# DCDC_12V_Servo.net
KiCad netlist of a schematic drawn in Altium Designer
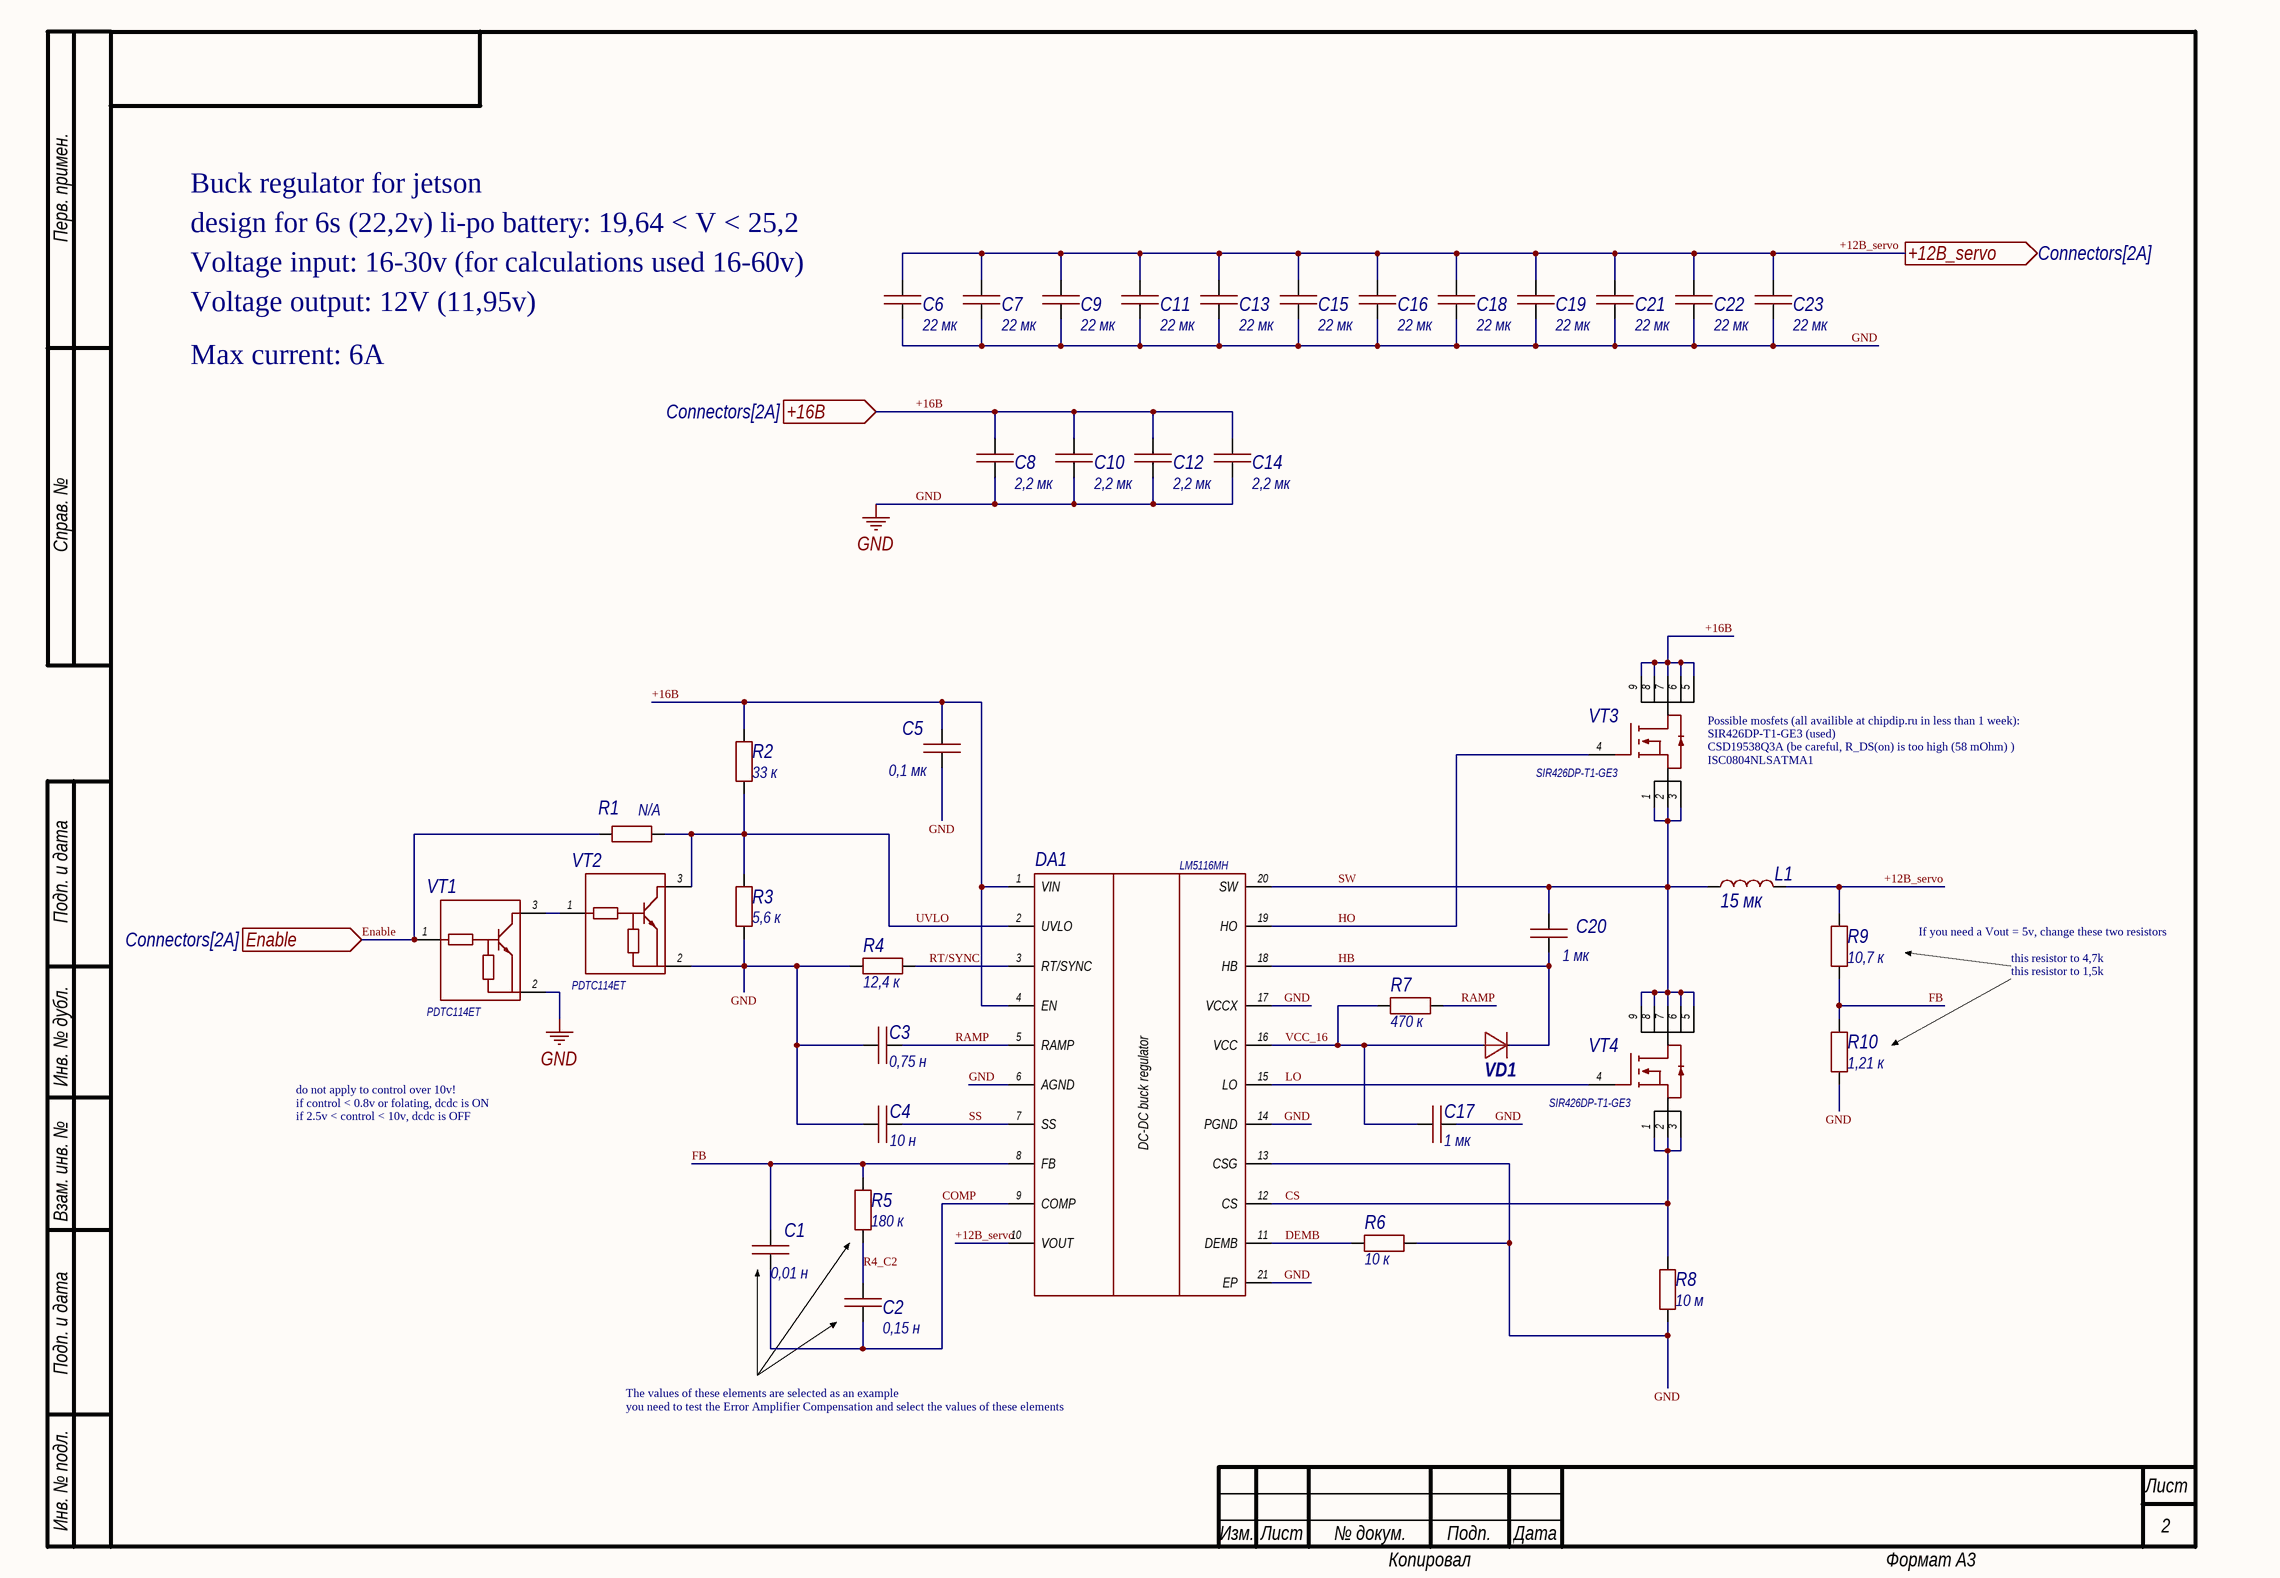
[diagram p0: DCDC_12V_Servo.SchDoc]

(export (version "E")
  (design (tool "Eeschema 10.0.6"))
  (components
    (comp (ref "C1")
      (value "0,01 н")
      (footprint "0603C")
      (description "Конденсатор")
      (fields
        (field (name "PART NUMBER") "Capacitor_0,01n_10_50V_X7R_0603C")
        (field (name "TOLERANCE") "0,1")
      )
      (libsource (lib "Hydrolib") (part "Capacitor"))
    )
    (comp (ref "C2")
      (value "0,15 н")
      (footprint "0603C")
      (description "Конденсатор")
      (fields
        (field (name "PART NUMBER") "Capacitor_0,15n_10_50V_X7R_0603C")
        (field (name "TOLERANCE") "0,1")
      )
      (libsource (lib "Hydrolib") (part "Capacitor"))
    )
    (comp (ref "C3")
      (value "0,75 н")
      (footprint "0603C")
      (description "Конденсатор")
      (fields
        (field (name "PART NUMBER") "Capacitor_0,75n_10_50V_X7R_0603C")
        (field (name "TOLERANCE") "0,1")
      )
      (libsource (lib "Hydrolib") (part "Capacitor"))
    )
    (comp (ref "C4")
      (value "10 н")
      (footprint "0603C")
      (description "Конденсатор")
      (fields (field (name "PART NUMBER") "Capacitor_10n_10_50V_X7R_0603C") (field (name "TOLERANCE") "0,1"))
      (libsource (lib "Hydrolib") (part "Capacitor"))
    )
    (comp (ref "C5")
      (value "0,1 мк")
      (footprint "0603C")
      (description "Конденсатор")
      (fields (field (name "PART NUMBER") "Capacitor_0,1u_10_50V_X7R_0603C") (field (name "TOLERANCE") "0,1"))
      (libsource (lib "Hydrolib") (part "Capacitor"))
    )
    (comp (ref "C6")
      (value "22 мк")
      (footprint "1210C")
      (description "Конденсатор")
      (fields (field (name "PART NUMBER") "Capacitor_22u_10_25V_X7R_1210C") (field (name "TOLERANCE") "0,1"))
      (libsource (lib "Hydrolib") (part "Capacitor"))
    )
    (comp (ref "C7")
      (value "22 мк")
      (footprint "1210C")
      (description "Конденсатор")
      (fields (field (name "PART NUMBER") "Capacitor_22u_10_25V_X7R_1210C") (field (name "TOLERANCE") "0,1"))
      (libsource (lib "Hydrolib") (part "Capacitor"))
    )
    (comp (ref "C8")
      (value "2,2 мк")
      (footprint "1206C")
      (description "Конденсатор")
      (fields (field (name "PART NUMBER") "Capacitor_2,2u_10_50V_X7R_1206C") (field (name "TOLERANCE") "0,1"))
      (libsource (lib "Hydrolib") (part "Capacitor"))
    )
    (comp (ref "C9")
      (value "22 мк")
      (footprint "1210C")
      (description "Конденсатор")
      (fields (field (name "PART NUMBER") "Capacitor_22u_10_25V_X7R_1210C") (field (name "TOLERANCE") "0,1"))
      (libsource (lib "Hydrolib") (part "Capacitor"))
    )
    (comp (ref "C10")
      (value "2,2 мк")
      (footprint "1206C")
      (description "Конденсатор")
      (fields (field (name "PART NUMBER") "Capacitor_2,2u_10_50V_X7R_1206C") (field (name "TOLERANCE") "0,1"))
      (libsource (lib "Hydrolib") (part "Capacitor"))
    )
    (comp (ref "C11")
      (value "22 мк")
      (footprint "1210C")
      (description "Конденсатор")
      (fields (field (name "PART NUMBER") "Capacitor_22u_10_25V_X7R_1210C") (field (name "TOLERANCE") "0,1"))
      (libsource (lib "Hydrolib") (part "Capacitor"))
    )
    (comp (ref "C12")
      (value "2,2 мк")
      (footprint "1206C")
      (description "Конденсатор")
      (fields (field (name "PART NUMBER") "Capacitor_2,2u_10_50V_X7R_1206C") (field (name "TOLERANCE") "0,1"))
      (libsource (lib "Hydrolib") (part "Capacitor"))
    )
    (comp (ref "C13")
      (value "22 мк")
      (footprint "1210C")
      (description "Конденсатор")
      (fields (field (name "PART NUMBER") "Capacitor_22u_10_25V_X7R_1210C") (field (name "TOLERANCE") "0,1"))
      (libsource (lib "Hydrolib") (part "Capacitor"))
    )
    (comp (ref "C14")
      (value "2,2 мк")
      (footprint "1206C")
      (description "Конденсатор")
      (fields (field (name "PART NUMBER") "Capacitor_2,2u_10_50V_X7R_1206C") (field (name "TOLERANCE") "0,1"))
      (libsource (lib "Hydrolib") (part "Capacitor"))
    )
    (comp (ref "C15")
      (value "22 мк")
      (footprint "1210C")
      (description "Конденсатор")
      (fields (field (name "PART NUMBER") "Capacitor_22u_10_25V_X7R_1210C") (field (name "TOLERANCE") "0,1"))
      (libsource (lib "Hydrolib") (part "Capacitor"))
    )
    (comp (ref "C16")
      (value "22 мк")
      (footprint "1210C")
      (description "Конденсатор")
      (fields (field (name "PART NUMBER") "Capacitor_22u_10_25V_X7R_1210C") (field (name "TOLERANCE") "0,1"))
      (libsource (lib "Hydrolib") (part "Capacitor"))
    )
    (comp (ref "C17")
      (value "1 мк")
      (footprint "0603C")
      (description "Конденсатор")
      (fields (field (name "PART NUMBER") "Capacitor_1u_10_50V_X7R_0603C") (field (name "TOLERANCE") "0,1"))
      (libsource (lib "Hydrolib") (part "Capacitor"))
    )
    (comp (ref "C18")
      (value "22 мк")
      (footprint "1210C")
      (description "Конденсатор")
      (fields (field (name "PART NUMBER") "Capacitor_22u_10_25V_X7R_1210C") (field (name "TOLERANCE") "0,1"))
      (libsource (lib "Hydrolib") (part "Capacitor"))
    )
    (comp (ref "C19")
      (value "22 мк")
      (footprint "1210C")
      (description "Конденсатор")
      (fields (field (name "PART NUMBER") "Capacitor_22u_10_25V_X7R_1210C") (field (name "TOLERANCE") "0,1"))
      (libsource (lib "Hydrolib") (part "Capacitor"))
    )
    (comp (ref "C20")
      (value "1 мк")
      (footprint "0603C")
      (description "Конденсатор")
      (fields (field (name "PART NUMBER") "Capacitor_1u_10_50V_X7R_0603C") (field (name "TOLERANCE") "0,1"))
      (libsource (lib "Hydrolib") (part "Capacitor"))
    )
    (comp (ref "C21")
      (value "22 мк")
      (footprint "1210C")
      (description "Конденсатор")
      (fields (field (name "PART NUMBER") "Capacitor_22u_10_25V_X7R_1210C") (field (name "TOLERANCE") "0,1"))
      (libsource (lib "Hydrolib") (part "Capacitor"))
    )
    (comp (ref "C22")
      (value "22 мк")
      (footprint "1210C")
      (description "Конденсатор")
      (fields (field (name "PART NUMBER") "Capacitor_22u_10_25V_X7R_1210C") (field (name "TOLERANCE") "0,1"))
      (libsource (lib "Hydrolib") (part "Capacitor"))
    )
    (comp (ref "C23")
      (value "22 мк")
      (footprint "1210C")
      (description "Конденсатор")
      (fields (field (name "PART NUMBER") "Capacitor_22u_10_25V_X7R_1210C") (field (name "TOLERANCE") "0,1"))
      (libsource (lib "Hydrolib") (part "Capacitor"))
    )
    (comp (ref "DA1")
      (value "LM5116MH")
      (footprint "HTSSOP-20")
      (description "dc-dc понижающий adj 6-100v")
      (fields (field (name "MANUFACTURER_PART_NUMBER") "LM5116MH/NOPB"))
      (libsource (lib "Hydrolib") (part "LM5116MH"))
    )
    (comp (ref "L1")
      (value "15 мк")
      (footprint "SPRH127")
      (description "Индуктивность на 15 мкГн, номинальный ток 8,4 А")
      (fields (field (name "PART NUMBER") "CDSPRH127-150M"))
      (libsource (lib "Hydrolib") (part "Inductance"))
    )
    (comp (ref "R1")
      (value "N/A")
      (footprint "0603R")
      (description "посадочное место 0603 под перемычку")
      (fields (field (name "PART NUMBER") "res_0603_N/A") (field (name "TOLERANCE") "1%"))
      (libsource (lib "Hydrolib") (part "Resistor"))
    )
    (comp (ref "R2")
      (value "33 к")
      (footprint "0603R")
      (description "Резистор номиналом 33 кОм и точностью 1%")
      (fields (field (name "PART NUMBER") "Resistor_33k_1_0603") (field (name "TOLERANCE") "1%"))
      (libsource (lib "") (part "Resistor_1"))
    )
    (comp (ref "R3")
      (value "5,6 к")
      (footprint "0603R")
      (description "Резистор номиналом 5,6 кОм 1%")
      (fields (field (name "PART NUMBER") "Resistor_5.6k_1_0603") (field (name "TOLERANCE") "1%"))
      (libsource (lib "") (part "Resistor_1"))
    )
    (comp (ref "R4")
      (value "12,4 к")
      (footprint "0603R")
      (description "Резистор номиналом 12,4 кОм и точностью 1%")
      (fields (field (name "PART NUMBER") "Resistor_12.4k_1_0603") (field (name "TOLERANCE") "1%"))
      (libsource (lib "Hydrolib") (part "Resistor"))
    )
    (comp (ref "R5")
      (value "180 к")
      (footprint "0603R")
      (description "Резистор номиналом 180 кОм и точностью 1%")
      (fields (field (name "PART NUMBER") "Resistor_180k_1_0603") (field (name "TOLERANCE") "1%"))
      (libsource (lib "") (part "Resistor_1"))
    )
    (comp (ref "R6")
      (value "10 к")
      (footprint "0603R")
      (description "Резистор номиналом 10 кОм и точностью 1%")
      (fields (field (name "PART NUMBER") "Resistor_10k_1_0603") (field (name "TOLERANCE") "1%"))
      (libsource (lib "Hydrolib") (part "Resistor"))
    )
    (comp (ref "R7")
      (value "470 к")
      (footprint "0603R")
      (description "Резистор номиналом 470 кОм и точностью 1%")
      (fields (field (name "PART NUMBER") "Resistor_470k_1_0603") (field (name "TOLERANCE") "1%"))
      (libsource (lib "Hydrolib") (part "Resistor"))
    )
    (comp (ref "R8")
      (value "10 м")
      (footprint "1210R")
      (description "Резистор номиналом 10 мОм, точностью 1%, 0.5Вт")
      (fields (field (name "PART NUMBER") "RL1210FR-070R01L") (field (name "TOLERANCE") "1%"))
      (libsource (lib "") (part "Resistor_1"))
    )
    (comp (ref "R9")
      (value "10,7 к")
      (footprint "0603R")
      (description "Резистор номиналом 10,7 кОм и точностью 1%")
      (fields (field (name "PART NUMBER") "Resistor_10.7k_1_0603") (field (name "TOLERANCE") "1%"))
      (libsource (lib "") (part "Resistor_1"))
    )
    (comp (ref "R10")
      (value "1,21 к")
      (footprint "0603R")
      (description "Резистор номиналом 1,21 кОм и точностью 1%")
      (fields (field (name "PART NUMBER") "Resistor_1.21k_1_0603") (field (name "TOLERANCE") "1%"))
      (libsource (lib "") (part "Resistor_1"))
    )
    (comp (ref "VD1")
      (value "ES1D-E3/61T")
      (footprint "SMA")
      (description "Диод 1A 200V")
      (libsource (lib "Hydrolib") (part "Rectifier_diode"))
    )
    (comp (ref "VT1")
      (value "PDTC114ET")
      (footprint "SOT23-3")
      (description "цифровой npn 50в 100мА")
      (libsource (lib "Hydrolib") (part "PDTC114ET"))
    )
    (comp (ref "VT2")
      (value "PDTC114ET")
      (footprint "SOT23-3")
      (description "цифровой npn 50в 100мА")
      (libsource (lib "Hydrolib") (part "PDTC114ET"))
    )
    (comp (ref "VT3")
      (value "SIR426DP-T1-GE3")
      (footprint "PowerPAK_SO-8")
      (description "Транзистор полевой MOSFET N-канальный 40В 41.7Вт")
      (libsource (lib "Hydrolib") (part "SIR426DP-T1-GE3"))
    )
    (comp (ref "VT4")
      (value "SIR426DP-T1-GE3")
      (footprint "PowerPAK_SO-8")
      (description "Транзистор полевой MOSFET N-канальный 40В 41.7Вт")
      (libsource (lib "Hydrolib") (part "SIR426DP-T1-GE3"))
    )
  )
  (nets
    (net (code "1") (name "/+12В_servo") (class "Default")
      (node (ref "C11") (pin "2") (pinfunction "2_2") (pintype "passive"))
      (node (ref "C13") (pin "2") (pinfunction "2_2") (pintype "passive"))
      (node (ref "C15") (pin "2") (pinfunction "2_2") (pintype "passive"))
      (node (ref "C16") (pin "2") (pinfunction "2_2") (pintype "passive"))
      (node (ref "C18") (pin "2") (pinfunction "2_2") (pintype "passive"))
      (node (ref "C19") (pin "2") (pinfunction "2_2") (pintype "passive"))
      (node (ref "C21") (pin "2") (pinfunction "2_2") (pintype "passive"))
      (node (ref "C22") (pin "2") (pinfunction "2_2") (pintype "passive"))
      (node (ref "C23") (pin "2") (pinfunction "2_2") (pintype "passive"))
      (node (ref "C6") (pin "2") (pinfunction "2_2") (pintype "passive"))
      (node (ref "C7") (pin "2") (pinfunction "2_2") (pintype "passive"))
      (node (ref "C9") (pin "2") (pinfunction "2_2") (pintype "passive"))
      (node (ref "DA1") (pin "10") (pinfunction "VOUT_10") (pintype "passive"))
      (node (ref "L1") (pin "2") (pinfunction "2_2") (pintype "passive"))
      (node (ref "R9") (pin "2") (pinfunction "2_2") (pintype "passive"))
    )
    (net (code "2") (name "/+16В") (class "Default")
      (node (ref "C10") (pin "2") (pinfunction "2_2") (pintype "passive"))
      (node (ref "C12") (pin "2") (pinfunction "2_2") (pintype "passive"))
      (node (ref "C14") (pin "2") (pinfunction "2_2") (pintype "passive"))
      (node (ref "C5") (pin "2") (pinfunction "2_2") (pintype "passive"))
      (node (ref "C8") (pin "2") (pinfunction "2_2") (pintype "passive"))
      (node (ref "DA1") (pin "1") (pinfunction "VIN_1") (pintype "passive"))
      (node (ref "DA1") (pin "4") (pinfunction "EN_4") (pintype "passive"))
      (node (ref "R2") (pin "2") (pinfunction "2_2") (pintype "passive"))
      (node (ref "VT3") (pin "5") (pinfunction "5_5") (pintype "passive"))
      (node (ref "VT3") (pin "6") (pinfunction "6_6") (pintype "passive"))
      (node (ref "VT3") (pin "7") (pinfunction "7_7") (pintype "passive"))
      (node (ref "VT3") (pin "8") (pinfunction "8_8") (pintype "passive"))
      (node (ref "VT3") (pin "9") (pinfunction "9_9") (pintype "passive"))
    )
    (net (code "3") (name "/COMP") (class "Default")
      (node (ref "C1") (pin "1") (pinfunction "1_1") (pintype "passive"))
      (node (ref "C2") (pin "1") (pinfunction "1_1") (pintype "passive"))
      (node (ref "DA1") (pin "9") (pinfunction "COMP_9") (pintype "passive"))
    )
    (net (code "4") (name "/CS") (class "Default")
      (node (ref "DA1") (pin "12") (pinfunction "CS_12") (pintype "passive"))
      (node (ref "R8") (pin "2") (pinfunction "2_2") (pintype "passive"))
      (node (ref "VT4") (pin "1") (pinfunction "1_1") (pintype "passive"))
      (node (ref "VT4") (pin "2") (pinfunction "2_2") (pintype "passive"))
      (node (ref "VT4") (pin "3") (pinfunction "3_3") (pintype "passive"))
    )
    (net (code "5") (name "/DEMB") (class "Default")
      (node (ref "DA1") (pin "11") (pinfunction "DEMB_11") (pintype "passive"))
      (node (ref "R6") (pin "1") (pinfunction "1_1") (pintype "passive"))
    )
    (net (code "6") (name "/Enable") (class "Default")
      (node (ref "R1") (pin "1") (pinfunction "1_1") (pintype "passive"))
      (node (ref "VT1") (pin "1") (pinfunction "B_1") (pintype "passive"))
    )
    (net (code "7") (name "/FB") (class "Default")
      (node (ref "C1") (pin "2") (pinfunction "2_2") (pintype "passive"))
      (node (ref "DA1") (pin "8") (pinfunction "FB_8") (pintype "passive"))
      (node (ref "R10") (pin "2") (pinfunction "2_2") (pintype "passive"))
      (node (ref "R5") (pin "2") (pinfunction "2_2") (pintype "passive"))
      (node (ref "R9") (pin "1") (pinfunction "1_1") (pintype "passive"))
    )
    (net (code "8") (name "/HB") (class "Default")
      (node (ref "C20") (pin "1") (pinfunction "1_1") (pintype "passive"))
      (node (ref "DA1") (pin "18") (pinfunction "HB_18") (pintype "passive"))
      (node (ref "VD1") (pin "2") (pinfunction "2_2") (pintype "passive"))
    )
    (net (code "9") (name "/HO") (class "Default")
      (node (ref "DA1") (pin "19") (pinfunction "HO_19") (pintype "passive"))
      (node (ref "VT3") (pin "4") (pinfunction "4_4") (pintype "passive"))
    )
    (net (code "10") (name "/LO") (class "Default")
      (node (ref "DA1") (pin "15") (pinfunction "LO_15") (pintype "passive"))
      (node (ref "VT4") (pin "4") (pinfunction "4_4") (pintype "passive"))
    )
    (net (code "11") (name "/R4_C2") (class "Default")
      (node (ref "C2") (pin "2") (pinfunction "2_2") (pintype "passive"))
      (node (ref "R5") (pin "1") (pinfunction "1_1") (pintype "passive"))
    )
    (net (code "12") (name "/RAMP") (class "Default")
      (node (ref "C3") (pin "2") (pinfunction "2_2") (pintype "passive"))
      (node (ref "DA1") (pin "5") (pinfunction "RAMP_5") (pintype "passive"))
      (node (ref "R7") (pin "2") (pinfunction "2_2") (pintype "passive"))
    )
    (net (code "13") (name "/RT{slash}SYNC") (class "Default")
      (node (ref "DA1") (pin "3") (pinfunction "RT/SYNC_3") (pintype "passive"))
      (node (ref "R4") (pin "2") (pinfunction "2_2") (pintype "passive"))
    )
    (net (code "14") (name "/SS") (class "Default")
      (node (ref "C4") (pin "2") (pinfunction "2_2") (pintype "passive"))
      (node (ref "DA1") (pin "7") (pinfunction "SS_7") (pintype "passive"))
    )
    (net (code "15") (name "/SW") (class "Default")
      (node (ref "C20") (pin "2") (pinfunction "2_2") (pintype "passive"))
      (node (ref "DA1") (pin "20") (pinfunction "SW_20") (pintype "passive"))
      (node (ref "L1") (pin "1") (pinfunction "1_1") (pintype "passive"))
      (node (ref "VT3") (pin "1") (pinfunction "1_1") (pintype "passive"))
      (node (ref "VT3") (pin "2") (pinfunction "2_2") (pintype "passive"))
      (node (ref "VT3") (pin "3") (pinfunction "3_3") (pintype "passive"))
      (node (ref "VT4") (pin "5") (pinfunction "5_5") (pintype "passive"))
      (node (ref "VT4") (pin "6") (pinfunction "6_6") (pintype "passive"))
      (node (ref "VT4") (pin "7") (pinfunction "7_7") (pintype "passive"))
      (node (ref "VT4") (pin "8") (pinfunction "8_8") (pintype "passive"))
      (node (ref "VT4") (pin "9") (pinfunction "9_9") (pintype "passive"))
    )
    (net (code "16") (name "/UVLO") (class "Default")
      (node (ref "DA1") (pin "2") (pinfunction "UVLO_2") (pintype "passive"))
      (node (ref "R1") (pin "2") (pinfunction "2_2") (pintype "passive"))
      (node (ref "R2") (pin "1") (pinfunction "1_1") (pintype "passive"))
      (node (ref "R3") (pin "2") (pinfunction "2_2") (pintype "passive"))
      (node (ref "VT2") (pin "3") (pinfunction "C_3") (pintype "passive"))
    )
    (net (code "17") (name "/VCC_16") (class "Default")
      (node (ref "C17") (pin "1") (pinfunction "1_1") (pintype "passive"))
      (node (ref "DA1") (pin "16") (pinfunction "VCC_16") (pintype "passive"))
      (node (ref "R7") (pin "1") (pinfunction "1_1") (pintype "passive"))
      (node (ref "VD1") (pin "1") (pinfunction "1_1") (pintype "passive"))
    )
    (net (code "18") (name "GND") (class "Default")
      (node (ref "C10") (pin "1") (pinfunction "1_1") (pintype "passive"))
      (node (ref "C11") (pin "1") (pinfunction "1_1") (pintype "passive"))
      (node (ref "C12") (pin "1") (pinfunction "1_1") (pintype "passive"))
      (node (ref "C13") (pin "1") (pinfunction "1_1") (pintype "passive"))
      (node (ref "C14") (pin "1") (pinfunction "1_1") (pintype "passive"))
      (node (ref "C15") (pin "1") (pinfunction "1_1") (pintype "passive"))
      (node (ref "C16") (pin "1") (pinfunction "1_1") (pintype "passive"))
      (node (ref "C17") (pin "2") (pinfunction "2_2") (pintype "passive"))
      (node (ref "C18") (pin "1") (pinfunction "1_1") (pintype "passive"))
      (node (ref "C19") (pin "1") (pinfunction "1_1") (pintype "passive"))
      (node (ref "C21") (pin "1") (pinfunction "1_1") (pintype "passive"))
      (node (ref "C22") (pin "1") (pinfunction "1_1") (pintype "passive"))
      (node (ref "C23") (pin "1") (pinfunction "1_1") (pintype "passive"))
      (node (ref "C3") (pin "1") (pinfunction "1_1") (pintype "passive"))
      (node (ref "C4") (pin "1") (pinfunction "1_1") (pintype "passive"))
      (node (ref "C5") (pin "1") (pinfunction "1_1") (pintype "passive"))
      (node (ref "C6") (pin "1") (pinfunction "1_1") (pintype "passive"))
      (node (ref "C7") (pin "1") (pinfunction "1_1") (pintype "passive"))
      (node (ref "C8") (pin "1") (pinfunction "1_1") (pintype "passive"))
      (node (ref "C9") (pin "1") (pinfunction "1_1") (pintype "passive"))
      (node (ref "DA1") (pin "13") (pinfunction "CSG_13") (pintype "passive"))
      (node (ref "DA1") (pin "14") (pinfunction "PGND_14") (pintype "passive"))
      (node (ref "DA1") (pin "17") (pinfunction "VCCX_17") (pintype "passive"))
      (node (ref "DA1") (pin "21") (pinfunction "EP_21") (pintype "passive"))
      (node (ref "DA1") (pin "6") (pinfunction "AGND_6") (pintype "passive"))
      (node (ref "R10") (pin "1") (pinfunction "1_1") (pintype "passive"))
      (node (ref "R3") (pin "1") (pinfunction "1_1") (pintype "passive"))
      (node (ref "R4") (pin "1") (pinfunction "1_1") (pintype "passive"))
      (node (ref "R6") (pin "2") (pinfunction "2_2") (pintype "passive"))
      (node (ref "R8") (pin "1") (pinfunction "1_1") (pintype "passive"))
      (node (ref "VT1") (pin "2") (pinfunction "E_2") (pintype "passive"))
      (node (ref "VT2") (pin "2") (pinfunction "E_2") (pintype "passive"))
    )
    (net (code "19") (name "Net-(VT1-C)") (class "Default")
      (node (ref "VT1") (pin "3") (pinfunction "C_3") (pintype "passive"))
      (node (ref "VT2") (pin "1") (pinfunction "B_1") (pintype "passive"))
    )
  )
)
